# Host.net
KiCad netlist of a schematic drawn in Altium Designer
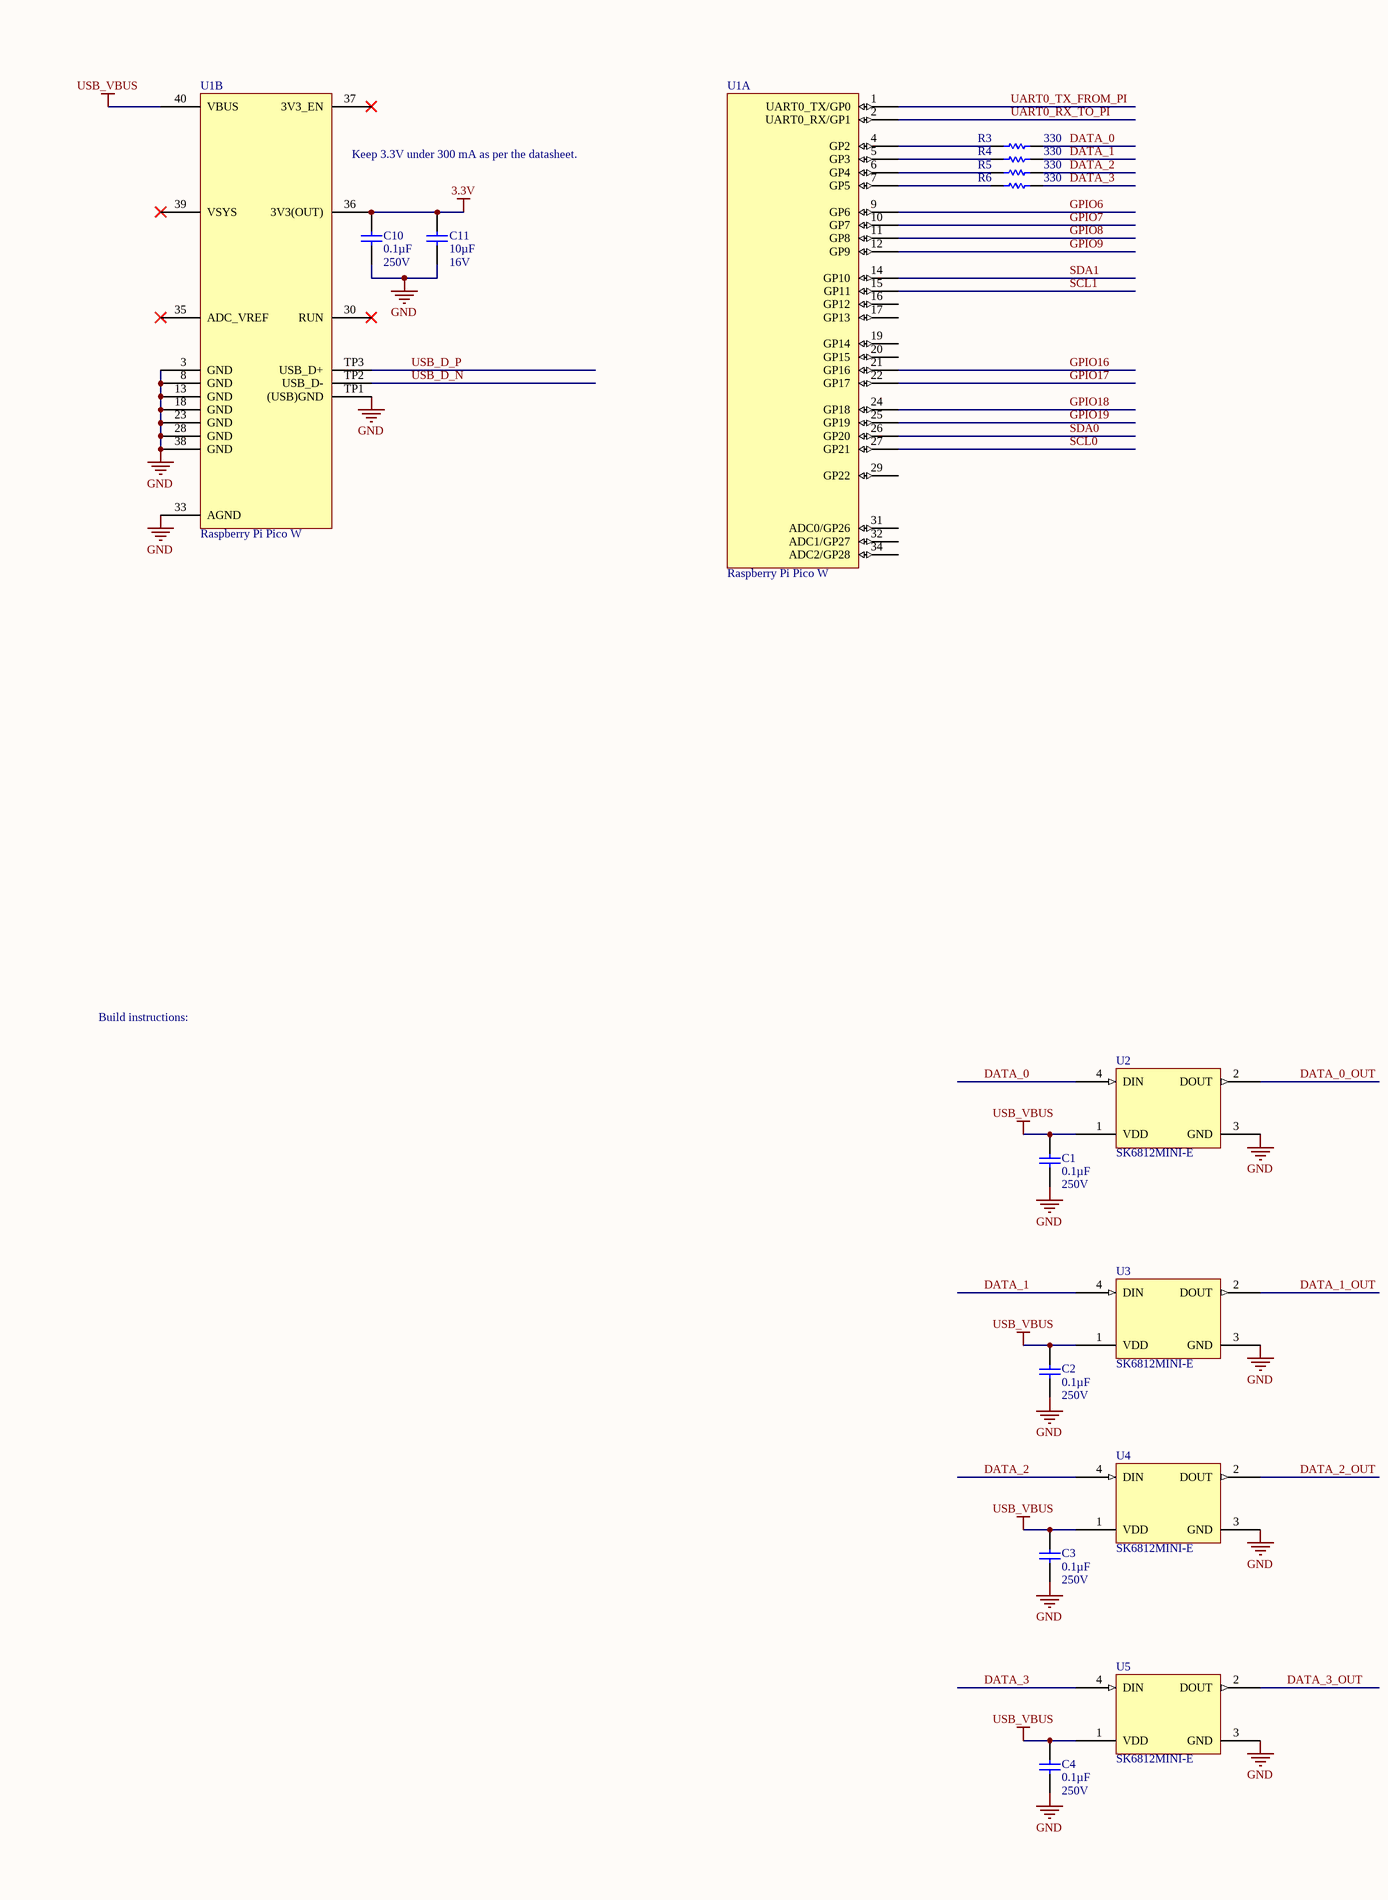
[diagram p0: Host.SchDoc, left]
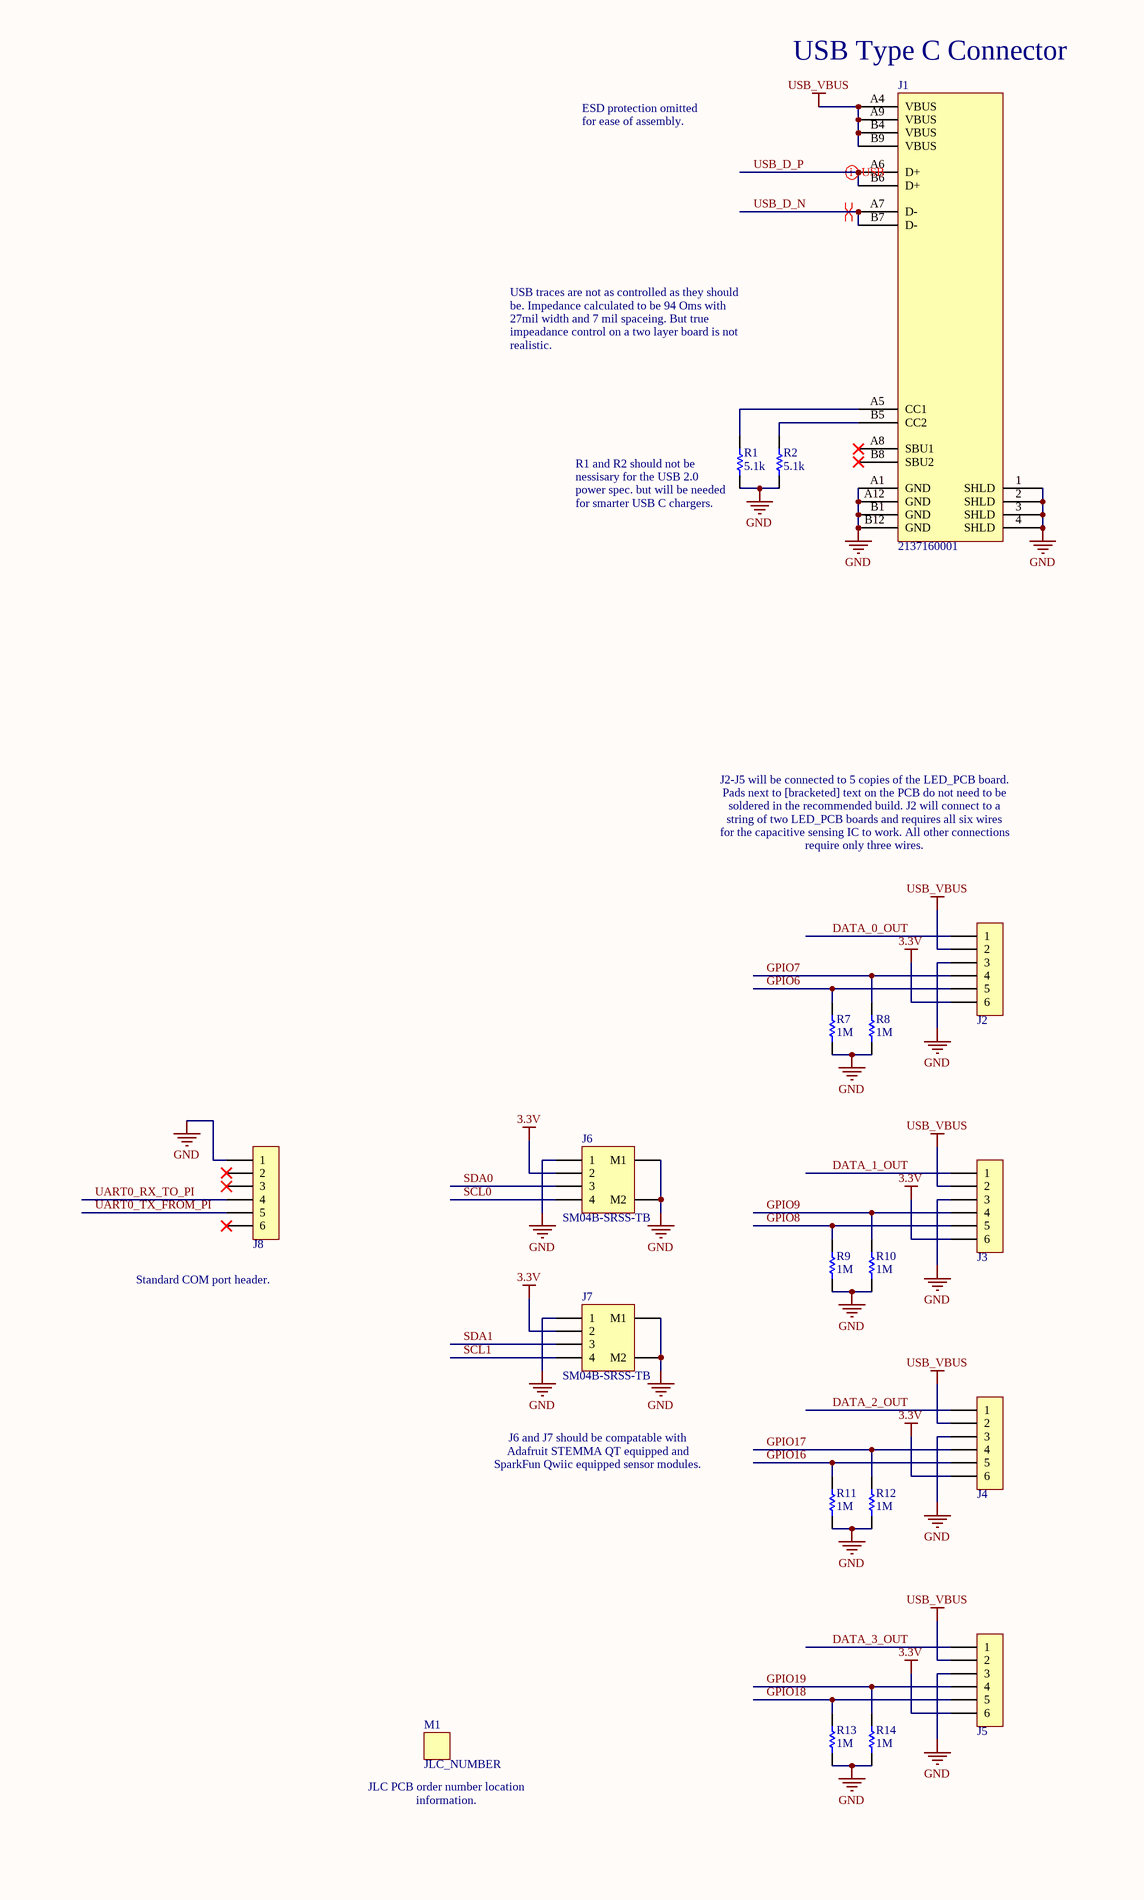
[diagram p1: Host.SchDoc, right]

(export (version "E")
  (design (tool "Eeschema 10.0.6"))
  (components
    (comp (ref "C1")
      (value "0.1µF")
      (footprint "Chip0805")
      (description "CAP CER 0.1UF 250V 10% X7T 0805")
      (fields
        (field (name "VOLTAGE") "250V")
        (field (name "PARTNUMBER") "C2012X7T2E104K125AA")
        (field (name "MANUFACTURER") "TDK Corporation")
      )
      (libsource (lib "Passives") (part "CAP"))
    )
    (comp (ref "C2")
      (value "0.1µF")
      (footprint "Chip0805")
      (description "CAP CER 0.1UF 250V 10% X7T 0805")
      (fields
        (field (name "VOLTAGE") "250V")
        (field (name "PARTNUMBER") "C2012X7T2E104K125AA")
        (field (name "MANUFACTURER") "TDK Corporation")
      )
      (libsource (lib "Passives") (part "CAP"))
    )
    (comp (ref "C3")
      (value "0.1µF")
      (footprint "Chip0805")
      (description "CAP CER 0.1UF 250V 10% X7T 0805")
      (fields
        (field (name "VOLTAGE") "250V")
        (field (name "PARTNUMBER") "C2012X7T2E104K125AA")
        (field (name "MANUFACTURER") "TDK Corporation")
      )
      (libsource (lib "Passives") (part "CAP"))
    )
    (comp (ref "C4")
      (value "0.1µF")
      (footprint "Chip0805")
      (description "CAP CER 0.1UF 250V 10% X7T 0805")
      (fields
        (field (name "VOLTAGE") "250V")
        (field (name "PARTNUMBER") "C2012X7T2E104K125AA")
        (field (name "MANUFACTURER") "TDK Corporation")
      )
      (libsource (lib "Passives") (part "CAP"))
    )
    (comp (ref "C10")
      (value "0.1µF")
      (footprint "Chip0805")
      (description "CAP CER 0.1UF 250V 10% X7T 0805")
      (fields
        (field (name "VOLTAGE") "250V")
        (field (name "PARTNUMBER") "C2012X7T2E104K125AA")
        (field (name "MANUFACTURER") "TDK Corporation")
      )
      (libsource (lib "Passives") (part "CAP"))
    )
    (comp (ref "C11")
      (value "10µF")
      (footprint "Chip0805")
      (description "CAP CER 10UF 16V 10% X5R 0805")
      (fields
        (field (name "VOLTAGE") "16V")
        (field (name "PARTNUMBER") "C2012X5R1C106K125AC")
        (field (name "MANUFACTURER") "TDK Corporation")
      )
      (libsource (lib "Passives") (part "CAP"))
    )
    (comp (ref "J1")
      (value "2137160001")
      (footprint "MOLEX_2137160001")
      (description "CONN RCPT USB2.0 TYPE C 24POS RA")
      (fields (field (name "MANUFACTURER") "Molex, LLC"))
      (libsource (lib "Connectors") (part "MOLEX_2137160001"))
    )
    (comp (ref "J2")
      (value "HEADER_1x6_NO_BOM")
      (footprint "HEADER_1x6_100mil_NP")
      (libsource (lib "Mechanical") (part "HEADER_1x6_NO_BOM"))
    )
    (comp (ref "J3")
      (value "HEADER_1x6_NO_BOM")
      (footprint "HEADER_1x6_100mil_NP")
      (libsource (lib "Mechanical") (part "HEADER_1x6_NO_BOM"))
    )
    (comp (ref "J4")
      (value "HEADER_1x6_NO_BOM")
      (footprint "HEADER_1x6_100mil_NP")
      (libsource (lib "Mechanical") (part "HEADER_1x6_NO_BOM"))
    )
    (comp (ref "J5")
      (value "HEADER_1x6_NO_BOM")
      (footprint "HEADER_1x6_100mil_NP")
      (libsource (lib "Mechanical") (part "HEADER_1x6_NO_BOM"))
    )
    (comp (ref "J6")
      (value "SM04B-SRSS-TB")
      (footprint "JST_SM04B-SRSS-TB")
      (description "CONN HEADER SMD R/A 4POS 1MM")
      (fields (field (name "MANUFACTURER") "JST Sales America Inc."))
      (libsource (lib "Connectors") (part "JST_SM04B-SRSS-TB"))
    )
    (comp (ref "J7")
      (value "SM04B-SRSS-TB")
      (footprint "JST_SM04B-SRSS-TB")
      (description "CONN HEADER SMD R/A 4POS 1MM")
      (fields (field (name "MANUFACTURER") "JST Sales America Inc."))
      (libsource (lib "Connectors") (part "JST_SM04B-SRSS-TB"))
    )
    (comp (ref "J8")
      (value "HEADER_1x6_NO_BOM")
      (footprint "HEADER_1x6_100mil_NP")
      (libsource (lib "Mechanical") (part "HEADER_1x6_NO_BOM"))
    )
    (comp (ref "M1")
      (value "JLC_NUMBER")
      (footprint "JLC_NUMBER")
      (description "JLC Order Number Location")
      (libsource (lib "Mechanical") (part "MECH_NO_BOM"))
    )
    (comp (ref "R1")
      (value "5.1k")
      (footprint "Chip0805")
      (description "RES 5.10K OHM 1/8W 1% 0805 SMD")
      (fields (field (name "PARTNUMBER") "CRCW08055K10FKEA") (field (name "MANUFACTURER") "Vishay Dale"))
      (libsource (lib "Passives") (part "RES"))
    )
    (comp (ref "R2")
      (value "5.1k")
      (footprint "Chip0805")
      (description "RES 5.10K OHM 1/8W 1% 0805 SMD")
      (fields (field (name "PARTNUMBER") "CRCW08055K10FKEA") (field (name "MANUFACTURER") "Vishay Dale"))
      (libsource (lib "Passives") (part "RES"))
    )
    (comp (ref "R3")
      (value "330")
      (footprint "Chip0805")
      (description "RES 330 OHM 1/8W 1% 0805 SMD")
      (fields (field (name "PARTNUMBER") "CRCW0805330RFKEA") (field (name "MANUFACTURER") "Vishay Dale"))
      (libsource (lib "Passives") (part "RES"))
    )
    (comp (ref "R4")
      (value "330")
      (footprint "Chip0805")
      (description "RES 330 OHM 1/8W 1% 0805 SMD")
      (fields (field (name "PARTNUMBER") "CRCW0805330RFKEA") (field (name "MANUFACTURER") "Vishay Dale"))
      (libsource (lib "Passives") (part "RES"))
    )
    (comp (ref "R5")
      (value "330")
      (footprint "Chip0805")
      (description "RES 330 OHM 1/8W 1% 0805 SMD")
      (fields (field (name "PARTNUMBER") "CRCW0805330RFKEA") (field (name "MANUFACTURER") "Vishay Dale"))
      (libsource (lib "Passives") (part "RES"))
    )
    (comp (ref "R6")
      (value "330")
      (footprint "Chip0805")
      (description "RES 330 OHM 1/8W 1% 0805 SMD")
      (fields (field (name "PARTNUMBER") "CRCW0805330RFKEA") (field (name "MANUFACTURER") "Vishay Dale"))
      (libsource (lib "Passives") (part "RES"))
    )
    (comp (ref "R7")
      (value "1M")
      (footprint "Chip0805")
      (description "RES 1.00M OHM 1/8W 1% 0805 SMD")
      (fields (field (name "PARTNUMBER") "CRCW08051M00FKEA") (field (name "MANUFACTURER") "Vishay Dale"))
      (libsource (lib "Passives") (part "RES"))
    )
    (comp (ref "R8")
      (value "1M")
      (footprint "Chip0805")
      (description "RES 1.00M OHM 1/8W 1% 0805 SMD")
      (fields (field (name "PARTNUMBER") "CRCW08051M00FKEA") (field (name "MANUFACTURER") "Vishay Dale"))
      (libsource (lib "Passives") (part "RES"))
    )
    (comp (ref "R9")
      (value "1M")
      (footprint "Chip0805")
      (description "RES 1.00M OHM 1/8W 1% 0805 SMD")
      (fields (field (name "PARTNUMBER") "CRCW08051M00FKEA") (field (name "MANUFACTURER") "Vishay Dale"))
      (libsource (lib "Passives") (part "RES"))
    )
    (comp (ref "R10")
      (value "1M")
      (footprint "Chip0805")
      (description "RES 1.00M OHM 1/8W 1% 0805 SMD")
      (fields (field (name "PARTNUMBER") "CRCW08051M00FKEA") (field (name "MANUFACTURER") "Vishay Dale"))
      (libsource (lib "Passives") (part "RES"))
    )
    (comp (ref "R11")
      (value "1M")
      (footprint "Chip0805")
      (description "RES 1.00M OHM 1/8W 1% 0805 SMD")
      (fields (field (name "PARTNUMBER") "CRCW08051M00FKEA") (field (name "MANUFACTURER") "Vishay Dale"))
      (libsource (lib "Passives") (part "RES"))
    )
    (comp (ref "R12")
      (value "1M")
      (footprint "Chip0805")
      (description "RES 1.00M OHM 1/8W 1% 0805 SMD")
      (fields (field (name "PARTNUMBER") "CRCW08051M00FKEA") (field (name "MANUFACTURER") "Vishay Dale"))
      (libsource (lib "Passives") (part "RES"))
    )
    (comp (ref "R13")
      (value "1M")
      (footprint "Chip0805")
      (description "RES 1.00M OHM 1/8W 1% 0805 SMD")
      (fields (field (name "PARTNUMBER") "CRCW08051M00FKEA") (field (name "MANUFACTURER") "Vishay Dale"))
      (libsource (lib "Passives") (part "RES"))
    )
    (comp (ref "R14")
      (value "1M")
      (footprint "Chip0805")
      (description "RES 1.00M OHM 1/8W 1% 0805 SMD")
      (fields (field (name "PARTNUMBER") "CRCW08051M00FKEA") (field (name "MANUFACTURER") "Vishay Dale"))
      (libsource (lib "Passives") (part "RES"))
    )
    (comp (ref "U1")
      (value "Raspberry Pi Pico W")
      (footprint "RASPBERRY_PI_PICO_W")
      (description "RASPBERRY PI PICO W")
      (fields (field (name "MANUFACTURER PART NUMBER") "SC0918") (field (name "MANUFACTURER") "Raspberry Pi"))
      (libsource (lib "ICs") (part "PI_PICO_SC0915"))
    )
    (comp (ref "U2")
      (value "SK6812MINI-E")
      (footprint "SK6812MINI-E")
      (description "Addressable RGB LED")
      (fields (field (name "MANUFACTURER") "Adafruit Industries LLC"))
      (libsource (lib "Optoelectronics") (part "SK6812MINI-E"))
    )
    (comp (ref "U3")
      (value "SK6812MINI-E")
      (footprint "SK6812MINI-E")
      (description "Addressable RGB LED")
      (fields (field (name "MANUFACTURER") "Adafruit Industries LLC"))
      (libsource (lib "Optoelectronics") (part "SK6812MINI-E"))
    )
    (comp (ref "U4")
      (value "SK6812MINI-E")
      (footprint "SK6812MINI-E")
      (description "Addressable RGB LED")
      (fields (field (name "MANUFACTURER") "Adafruit Industries LLC"))
      (libsource (lib "Optoelectronics") (part "SK6812MINI-E"))
    )
    (comp (ref "U5")
      (value "SK6812MINI-E")
      (footprint "SK6812MINI-E")
      (description "Addressable RGB LED")
      (fields (field (name "MANUFACTURER") "Adafruit Industries LLC"))
      (libsource (lib "Optoelectronics") (part "SK6812MINI-E"))
    )
  )
  (nets
    (net (code "1") (name "/DATA_0") (class "Default")
      (node (ref "R3") (pin "2") (pinfunction "2_2") (pintype "passive"))
      (node (ref "U2") (pin "4") (pinfunction "DIN_4") (pintype "input"))
    )
    (net (code "2") (name "/DATA_0_OUT") (class "Default")
      (node (ref "J2") (pin "1") (pinfunction "1_1") (pintype "passive"))
      (node (ref "U2") (pin "2") (pinfunction "DOUT_2") (pintype "output"))
    )
    (net (code "3") (name "/DATA_1") (class "Default")
      (node (ref "R4") (pin "2") (pinfunction "2_2") (pintype "passive"))
      (node (ref "U3") (pin "4") (pinfunction "DIN_4") (pintype "input"))
    )
    (net (code "4") (name "/DATA_1_OUT") (class "Default")
      (node (ref "J3") (pin "1") (pinfunction "1_1") (pintype "passive"))
      (node (ref "U3") (pin "2") (pinfunction "DOUT_2") (pintype "output"))
    )
    (net (code "5") (name "/DATA_2") (class "Default")
      (node (ref "R5") (pin "2") (pinfunction "2_2") (pintype "passive"))
      (node (ref "U4") (pin "4") (pinfunction "DIN_4") (pintype "input"))
    )
    (net (code "6") (name "/DATA_2_OUT") (class "Default")
      (node (ref "J4") (pin "1") (pinfunction "1_1") (pintype "passive"))
      (node (ref "U4") (pin "2") (pinfunction "DOUT_2") (pintype "output"))
    )
    (net (code "7") (name "/DATA_3") (class "Default")
      (node (ref "R6") (pin "2") (pinfunction "2_2") (pintype "passive"))
      (node (ref "U5") (pin "4") (pinfunction "DIN_4") (pintype "input"))
    )
    (net (code "8") (name "/DATA_3_OUT") (class "Default")
      (node (ref "J5") (pin "1") (pinfunction "1_1") (pintype "passive"))
      (node (ref "U5") (pin "2") (pinfunction "DOUT_2") (pintype "output"))
    )
    (net (code "9") (name "/GPIO6") (class "Default")
      (node (ref "J2") (pin "5") (pinfunction "5_5") (pintype "passive"))
      (node (ref "R7") (pin "2") (pinfunction "2_2") (pintype "passive"))
      (node (ref "U1") (pin "9") (pinfunction "GP6_9") (pintype "bidirectional"))
    )
    (net (code "10") (name "/GPIO7") (class "Default")
      (node (ref "J2") (pin "4") (pinfunction "4_4") (pintype "passive"))
      (node (ref "R8") (pin "2") (pinfunction "2_2") (pintype "passive"))
      (node (ref "U1") (pin "10") (pinfunction "GP7_10") (pintype "bidirectional"))
    )
    (net (code "11") (name "/GPIO8") (class "Default")
      (node (ref "J3") (pin "5") (pinfunction "5_5") (pintype "passive"))
      (node (ref "R9") (pin "2") (pinfunction "2_2") (pintype "passive"))
      (node (ref "U1") (pin "11") (pinfunction "GP8_11") (pintype "bidirectional"))
    )
    (net (code "12") (name "/GPIO9") (class "Default")
      (node (ref "J3") (pin "4") (pinfunction "4_4") (pintype "passive"))
      (node (ref "R10") (pin "2") (pinfunction "2_2") (pintype "passive"))
      (node (ref "U1") (pin "12") (pinfunction "GP9_12") (pintype "bidirectional"))
    )
    (net (code "13") (name "/GPIO16") (class "Default")
      (node (ref "J4") (pin "5") (pinfunction "5_5") (pintype "passive"))
      (node (ref "R11") (pin "2") (pinfunction "2_2") (pintype "passive"))
      (node (ref "U1") (pin "21") (pinfunction "GP16_21") (pintype "bidirectional"))
    )
    (net (code "14") (name "/GPIO17") (class "Default")
      (node (ref "J4") (pin "4") (pinfunction "4_4") (pintype "passive"))
      (node (ref "R12") (pin "2") (pinfunction "2_2") (pintype "passive"))
      (node (ref "U1") (pin "22") (pinfunction "GP17_22") (pintype "bidirectional"))
    )
    (net (code "15") (name "/GPIO18") (class "Default")
      (node (ref "J5") (pin "5") (pinfunction "5_5") (pintype "passive"))
      (node (ref "R13") (pin "2") (pinfunction "2_2") (pintype "passive"))
      (node (ref "U1") (pin "24") (pinfunction "GP18_24") (pintype "bidirectional"))
    )
    (net (code "16") (name "/GPIO19") (class "Default")
      (node (ref "J5") (pin "4") (pinfunction "4_4") (pintype "passive"))
      (node (ref "R14") (pin "2") (pinfunction "2_2") (pintype "passive"))
      (node (ref "U1") (pin "25") (pinfunction "GP19_25") (pintype "bidirectional"))
    )
    (net (code "17") (name "/SCL0") (class "Default")
      (node (ref "J6") (pin "4") (pinfunction "4_4") (pintype "passive"))
      (node (ref "U1") (pin "27") (pinfunction "GP21_27") (pintype "bidirectional"))
    )
    (net (code "18") (name "/SCL1") (class "Default")
      (node (ref "J7") (pin "4") (pinfunction "4_4") (pintype "passive"))
      (node (ref "U1") (pin "15") (pinfunction "GP11_15") (pintype "bidirectional"))
    )
    (net (code "19") (name "/SDA0") (class "Default")
      (node (ref "J6") (pin "3") (pinfunction "3_3") (pintype "passive"))
      (node (ref "U1") (pin "26") (pinfunction "GP20_26") (pintype "bidirectional"))
    )
    (net (code "20") (name "/SDA1") (class "Default")
      (node (ref "J7") (pin "3") (pinfunction "3_3") (pintype "passive"))
      (node (ref "U1") (pin "14") (pinfunction "GP10_14") (pintype "bidirectional"))
    )
    (net (code "21") (name "/UART0_RX_TO_PI") (class "Default")
      (node (ref "J8") (pin "4") (pinfunction "4_4") (pintype "passive"))
      (node (ref "U1") (pin "2") (pinfunction "UART0_RX/GP1_2") (pintype "bidirectional"))
    )
    (net (code "22") (name "/UART0_TX_FROM_PI") (class "Default")
      (node (ref "J8") (pin "5") (pinfunction "5_5") (pintype "passive"))
      (node (ref "U1") (pin "1") (pinfunction "UART0_TX/GP0_1") (pintype "bidirectional"))
    )
    (net (code "23") (name "/USB_D_N") (class "Default")
      (node (ref "J1") (pin "A7") (pinfunction "D-_A7") (pintype "passive"))
      (node (ref "J1") (pin "B7") (pinfunction "D-_B7") (pintype "passive"))
      (node (ref "U1") (pin "TP2") (pinfunction "USB_D-_TP2") (pintype "passive"))
    )
    (net (code "24") (name "/USB_D_P") (class "Default")
      (node (ref "J1") (pin "A6") (pinfunction "D+_A6") (pintype "passive"))
      (node (ref "J1") (pin "B6") (pinfunction "D+_B6") (pintype "passive"))
      (node (ref "U1") (pin "TP3") (pinfunction "USB_D+_TP3") (pintype "passive"))
    )
    (net (code "25") (name "3.3V") (class "Default")
      (node (ref "C10") (pin "2") (pinfunction "2_2") (pintype "passive"))
      (node (ref "C11") (pin "2") (pinfunction "2_2") (pintype "passive"))
      (node (ref "J2") (pin "6") (pinfunction "6_6") (pintype "passive"))
      (node (ref "J3") (pin "6") (pinfunction "6_6") (pintype "passive"))
      (node (ref "J4") (pin "6") (pinfunction "6_6") (pintype "passive"))
      (node (ref "J5") (pin "6") (pinfunction "6_6") (pintype "passive"))
      (node (ref "J6") (pin "2") (pinfunction "2_2") (pintype "passive"))
      (node (ref "J7") (pin "2") (pinfunction "2_2") (pintype "passive"))
      (node (ref "U1") (pin "36") (pinfunction "3V3(OUT)_36") (pintype "passive"))
    )
    (net (code "26") (name "GND") (class "Default")
      (node (ref "C1") (pin "1") (pinfunction "1_1") (pintype "passive"))
      (node (ref "C10") (pin "1") (pinfunction "1_1") (pintype "passive"))
      (node (ref "C11") (pin "1") (pinfunction "1_1") (pintype "passive"))
      (node (ref "C2") (pin "1") (pinfunction "1_1") (pintype "passive"))
      (node (ref "C3") (pin "1") (pinfunction "1_1") (pintype "passive"))
      (node (ref "C4") (pin "1") (pinfunction "1_1") (pintype "passive"))
      (node (ref "J1") (pin "1") (pinfunction "SHLD_1") (pintype "passive"))
      (node (ref "J1") (pin "2") (pinfunction "SHLD_2") (pintype "passive"))
      (node (ref "J1") (pin "3") (pinfunction "SHLD_3") (pintype "passive"))
      (node (ref "J1") (pin "4") (pinfunction "SHLD_4") (pintype "passive"))
      (node (ref "J1") (pin "A1") (pinfunction "GND_A1") (pintype "passive"))
      (node (ref "J1") (pin "A12") (pinfunction "GND_A12") (pintype "passive"))
      (node (ref "J1") (pin "B1") (pinfunction "GND_B1") (pintype "passive"))
      (node (ref "J1") (pin "B12") (pinfunction "GND_B12") (pintype "passive"))
      (node (ref "J2") (pin "3") (pinfunction "3_3") (pintype "passive"))
      (node (ref "J3") (pin "3") (pinfunction "3_3") (pintype "passive"))
      (node (ref "J4") (pin "3") (pinfunction "3_3") (pintype "passive"))
      (node (ref "J5") (pin "3") (pinfunction "3_3") (pintype "passive"))
      (node (ref "J6") (pin "1") (pinfunction "1_1") (pintype "passive"))
      (node (ref "J6") (pin "M1") (pinfunction "M1_M1") (pintype "passive"))
      (node (ref "J6") (pin "M2") (pinfunction "M2_M2") (pintype "passive"))
      (node (ref "J7") (pin "1") (pinfunction "1_1") (pintype "passive"))
      (node (ref "J7") (pin "M1") (pinfunction "M1_M1") (pintype "passive"))
      (node (ref "J7") (pin "M2") (pinfunction "M2_M2") (pintype "passive"))
      (node (ref "J8") (pin "1") (pinfunction "1_1") (pintype "passive"))
      (node (ref "R1") (pin "1") (pinfunction "1_1") (pintype "passive"))
      (node (ref "R10") (pin "1") (pinfunction "1_1") (pintype "passive"))
      (node (ref "R11") (pin "1") (pinfunction "1_1") (pintype "passive"))
      (node (ref "R12") (pin "1") (pinfunction "1_1") (pintype "passive"))
      (node (ref "R13") (pin "1") (pinfunction "1_1") (pintype "passive"))
      (node (ref "R14") (pin "1") (pinfunction "1_1") (pintype "passive"))
      (node (ref "R2") (pin "1") (pinfunction "1_1") (pintype "passive"))
      (node (ref "R7") (pin "1") (pinfunction "1_1") (pintype "passive"))
      (node (ref "R8") (pin "1") (pinfunction "1_1") (pintype "passive"))
      (node (ref "R9") (pin "1") (pinfunction "1_1") (pintype "passive"))
      (node (ref "U1") (pin "13") (pinfunction "GND_13") (pintype "passive"))
      (node (ref "U1") (pin "18") (pinfunction "GND_18") (pintype "passive"))
      (node (ref "U1") (pin "23") (pinfunction "GND_23") (pintype "passive"))
      (node (ref "U1") (pin "28") (pinfunction "GND_28") (pintype "passive"))
      (node (ref "U1") (pin "3") (pinfunction "GND_3") (pintype "passive"))
      (node (ref "U1") (pin "33") (pinfunction "AGND_33") (pintype "passive"))
      (node (ref "U1") (pin "38") (pinfunction "GND_38") (pintype "passive"))
      (node (ref "U1") (pin "8") (pinfunction "GND_8") (pintype "passive"))
      (node (ref "U1") (pin "TP1") (pinfunction "(USB)GND_TP1") (pintype "passive"))
      (node (ref "U2") (pin "3") (pinfunction "GND_3") (pintype "passive"))
      (node (ref "U3") (pin "3") (pinfunction "GND_3") (pintype "passive"))
      (node (ref "U4") (pin "3") (pinfunction "GND_3") (pintype "passive"))
      (node (ref "U5") (pin "3") (pinfunction "GND_3") (pintype "passive"))
    )
    (net (code "27") (name "Net-(J1-CC1)") (class "Default")
      (node (ref "J1") (pin "A5") (pinfunction "CC1_A5") (pintype "passive"))
      (node (ref "R1") (pin "2") (pinfunction "2_2") (pintype "passive"))
    )
    (net (code "28") (name "Net-(J1-CC2)") (class "Default")
      (node (ref "J1") (pin "B5") (pinfunction "CC2_B5") (pintype "passive"))
      (node (ref "R2") (pin "2") (pinfunction "2_2") (pintype "passive"))
    )
    (net (code "29") (name "Net-(U1A-GP2)") (class "Default")
      (node (ref "R3") (pin "1") (pinfunction "1_1") (pintype "passive"))
      (node (ref "U1") (pin "4") (pinfunction "GP2_4") (pintype "bidirectional"))
    )
    (net (code "30") (name "Net-(U1A-GP3)") (class "Default")
      (node (ref "R4") (pin "1") (pinfunction "1_1") (pintype "passive"))
      (node (ref "U1") (pin "5") (pinfunction "GP3_5") (pintype "bidirectional"))
    )
    (net (code "31") (name "Net-(U1A-GP4)") (class "Default")
      (node (ref "R5") (pin "1") (pinfunction "1_1") (pintype "passive"))
      (node (ref "U1") (pin "6") (pinfunction "GP4_6") (pintype "bidirectional"))
    )
    (net (code "32") (name "Net-(U1A-GP5)") (class "Default")
      (node (ref "R6") (pin "1") (pinfunction "1_1") (pintype "passive"))
      (node (ref "U1") (pin "7") (pinfunction "GP5_7") (pintype "bidirectional"))
    )
    (net (code "33") (name "USB_VBUS") (class "Default")
      (node (ref "C1") (pin "2") (pinfunction "2_2") (pintype "passive"))
      (node (ref "C2") (pin "2") (pinfunction "2_2") (pintype "passive"))
      (node (ref "C3") (pin "2") (pinfunction "2_2") (pintype "passive"))
      (node (ref "C4") (pin "2") (pinfunction "2_2") (pintype "passive"))
      (node (ref "J1") (pin "A4") (pinfunction "VBUS_A4") (pintype "passive"))
      (node (ref "J1") (pin "A9") (pinfunction "VBUS_A9") (pintype "passive"))
      (node (ref "J1") (pin "B4") (pinfunction "VBUS_B4") (pintype "passive"))
      (node (ref "J1") (pin "B9") (pinfunction "VBUS_B9") (pintype "passive"))
      (node (ref "J2") (pin "2") (pinfunction "2_2") (pintype "passive"))
      (node (ref "J3") (pin "2") (pinfunction "2_2") (pintype "passive"))
      (node (ref "J4") (pin "2") (pinfunction "2_2") (pintype "passive"))
      (node (ref "J5") (pin "2") (pinfunction "2_2") (pintype "passive"))
      (node (ref "U1") (pin "40") (pinfunction "VBUS_40") (pintype "passive"))
      (node (ref "U2") (pin "1") (pinfunction "VDD_1") (pintype "passive"))
      (node (ref "U3") (pin "1") (pinfunction "VDD_1") (pintype "passive"))
      (node (ref "U4") (pin "1") (pinfunction "VDD_1") (pintype "passive"))
      (node (ref "U5") (pin "1") (pinfunction "VDD_1") (pintype "passive"))
    )
    (net (code "34") (name "unconnected-(J1-SBU1-PadA8)") (class "Default")
      (node (ref "J1") (pin "A8") (pinfunction "SBU1_A8") (pintype "passive+no_connect"))
    )
    (net (code "35") (name "unconnected-(J1-SBU2-PadB8)") (class "Default")
      (node (ref "J1") (pin "B8") (pinfunction "SBU2_B8") (pintype "passive+no_connect"))
    )
    (net (code "36") (name "unconnected-(J8-Pad2)") (class "Default")
      (node (ref "J8") (pin "2") (pinfunction "2_2") (pintype "passive+no_connect"))
    )
    (net (code "37") (name "unconnected-(J8-Pad3)") (class "Default")
      (node (ref "J8") (pin "3") (pinfunction "3_3") (pintype "passive+no_connect"))
    )
    (net (code "38") (name "unconnected-(J8-Pad6)") (class "Default")
      (node (ref "J8") (pin "6") (pinfunction "6_6") (pintype "passive+no_connect"))
    )
    (net (code "39") (name "unconnected-(U1A-ADC0{slash}GP26-Pad31)") (class "Default")
      (node (ref "U1") (pin "31") (pinfunction "ADC0/GP26_31") (pintype "bidirectional"))
    )
    (net (code "40") (name "unconnected-(U1A-ADC1{slash}GP27-Pad32)") (class "Default")
      (node (ref "U1") (pin "32") (pinfunction "ADC1/GP27_32") (pintype "bidirectional"))
    )
    (net (code "41") (name "unconnected-(U1A-ADC2{slash}GP28-Pad34)") (class "Default")
      (node (ref "U1") (pin "34") (pinfunction "ADC2/GP28_34") (pintype "bidirectional"))
    )
    (net (code "42") (name "unconnected-(U1A-GP12-Pad16)") (class "Default")
      (node (ref "U1") (pin "16") (pinfunction "GP12_16") (pintype "bidirectional"))
    )
    (net (code "43") (name "unconnected-(U1A-GP13-Pad17)") (class "Default")
      (node (ref "U1") (pin "17") (pinfunction "GP13_17") (pintype "bidirectional"))
    )
    (net (code "44") (name "unconnected-(U1A-GP14-Pad19)") (class "Default")
      (node (ref "U1") (pin "19") (pinfunction "GP14_19") (pintype "bidirectional"))
    )
    (net (code "45") (name "unconnected-(U1A-GP15-Pad20)") (class "Default")
      (node (ref "U1") (pin "20") (pinfunction "GP15_20") (pintype "bidirectional"))
    )
    (net (code "46") (name "unconnected-(U1A-GP22-Pad29)") (class "Default")
      (node (ref "U1") (pin "29") (pinfunction "GP22_29") (pintype "bidirectional"))
    )
    (net (code "47") (name "unconnected-(U1B-3V3_EN-Pad37)") (class "Default")
      (node (ref "U1") (pin "37") (pinfunction "3V3_EN_37") (pintype "passive+no_connect"))
    )
    (net (code "48") (name "unconnected-(U1B-ADC_VREF-Pad35)") (class "Default")
      (node (ref "U1") (pin "35") (pinfunction "ADC_VREF_35") (pintype "passive+no_connect"))
    )
    (net (code "49") (name "unconnected-(U1B-RUN-Pad30)") (class "Default")
      (node (ref "U1") (pin "30") (pinfunction "RUN_30") (pintype "passive+no_connect"))
    )
    (net (code "50") (name "unconnected-(U1B-VSYS-Pad39)") (class "Default")
      (node (ref "U1") (pin "39") (pinfunction "VSYS_39") (pintype "passive+no_connect"))
    )
  )
)
